# DDC.net
KiCad netlist of a schematic drawn in Altium Designer
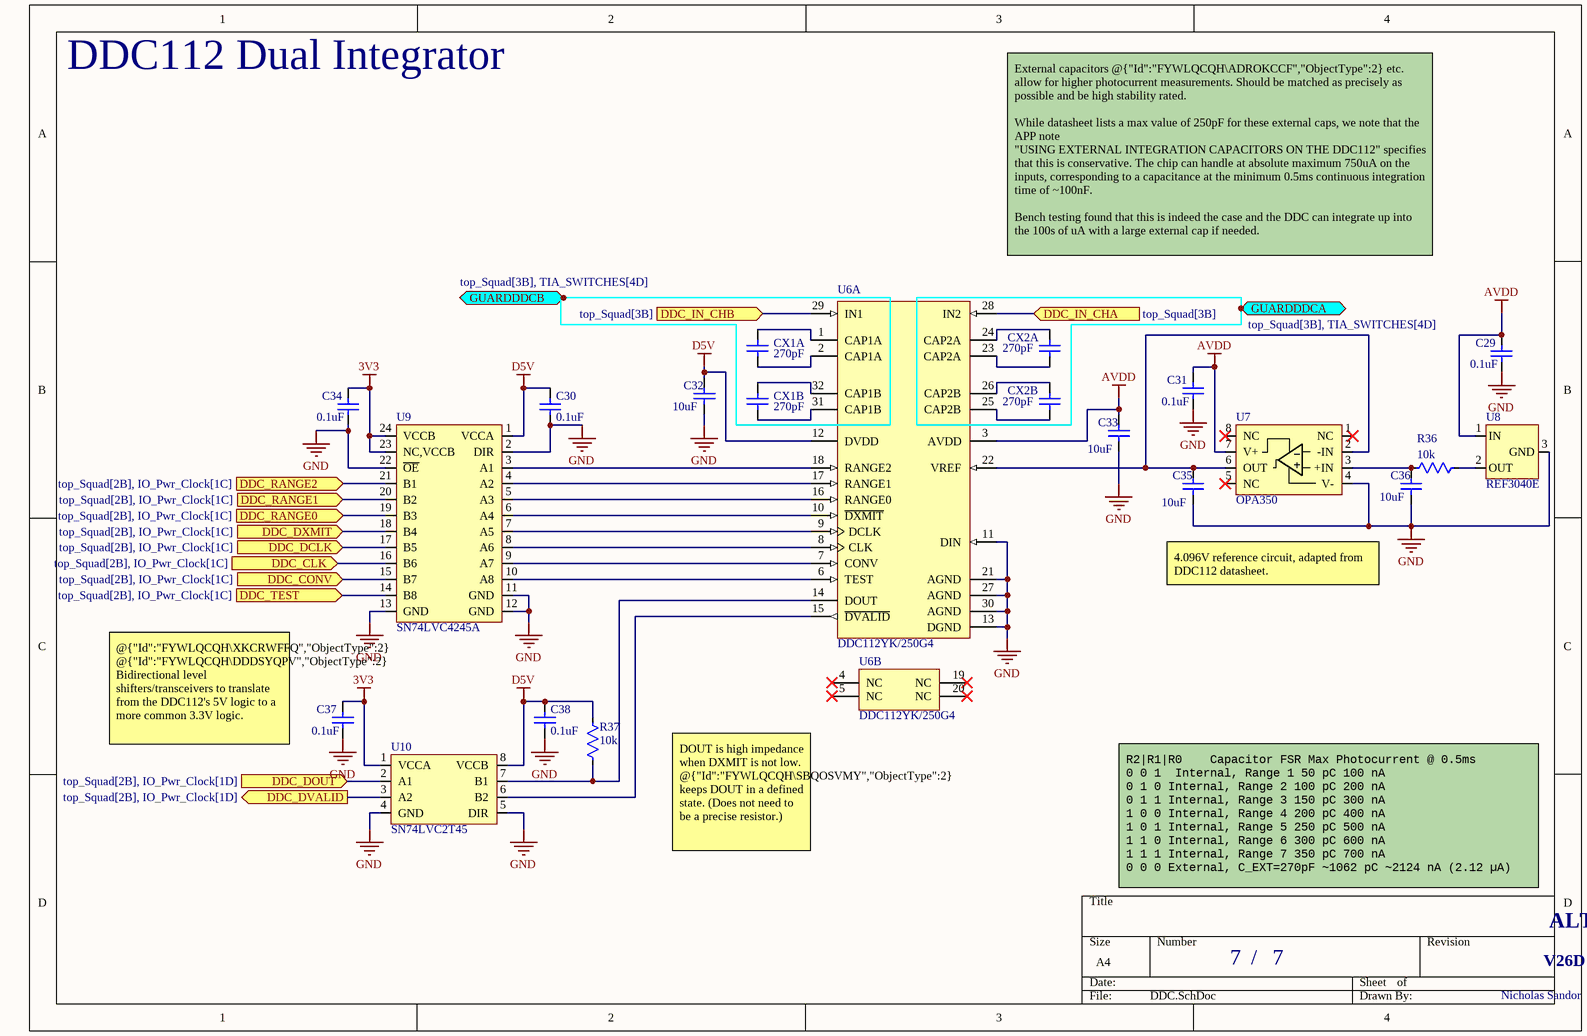
[diagram p0: DDC.SchDoc]

(export (version "E")
  (design (tool "Eeschema 10.0.6"))
  (components
    (comp (ref "C29")
      (value "0.1uF")
      (footprint "CAP 0603 IPC MID DENSITY")
      (description "Kemet C0603C104K5RACAUTO - Cap Ceramic 0.1uF 50V X7R 10% 0603 125C Paper T/R")
      (fields (field (name "MF") "KEMET") (field (name "MP") "C0603C104K5RACAUTO"))
      (libsource (lib "DDC112_Components") (part "CAP"))
    )
    (comp (ref "C30")
      (value "0.1uF")
      (footprint "CAP 0603 IPC MID DENSITY")
      (description "Kemet C0603C104K5RACAUTO - Cap Ceramic 0.1uF 50V X7R 10% 0603 125C Paper T/R")
      (fields (field (name "MF") "KEMET") (field (name "MP") "C0603C104K5RACAUTO"))
      (libsource (lib "DDC112_Components") (part "CAP"))
    )
    (comp (ref "C31")
      (value "0.1uF")
      (footprint "CAP 0603 IPC MID DENSITY")
      (description "Kemet C0603C104K5RACAUTO - Cap Ceramic 0.1uF 50V X7R 10% 0603 125C Paper T/R")
      (fields (field (name "MF") "KEMET") (field (name "MP") "C0603C104K5RACAUTO"))
      (libsource (lib "DDC112_Components") (part "CAP"))
    )
    (comp (ref "C32")
      (value "10uF")
      (footprint "CAP 0805 IPC MID DENSITY")
      (description "Murata GRM21BR61E106KA73L - Cap Ceramic 10uF 10% 25V X5R 0805")
      (fields (field (name "MF") "Murata") (field (name "MP") "GRM21BR61E106KA73L"))
      (libsource (lib "DDC112_Components") (part "CAP"))
    )
    (comp (ref "C33")
      (value "10uF")
      (footprint "CAP 0805 IPC MID DENSITY")
      (description "Murata GRM21BR61E106KA73L - Cap Ceramic 10uF 10% 25V X5R 0805")
      (fields (field (name "MF") "Murata") (field (name "MP") "GRM21BR61E106KA73L"))
      (libsource (lib "DDC112_Components") (part "CAP"))
    )
    (comp (ref "C34")
      (value "0.1uF")
      (footprint "CAP 0603 IPC MID DENSITY")
      (description "Kemet C0603C104K5RACAUTO - Cap Ceramic 0.1uF 50V X7R 10% 0603 125C Paper T/R")
      (fields (field (name "MF") "KEMET") (field (name "MP") "C0603C104K5RACAUTO"))
      (libsource (lib "DDC112_Components") (part "CAP"))
    )
    (comp (ref "C35")
      (value "10uF")
      (footprint "CAP 0805 IPC MID DENSITY")
      (description "Murata GRM21BR61E106KA73L - Cap Ceramic 10uF 10% 25V X5R 0805")
      (fields (field (name "MF") "Murata") (field (name "MP") "GRM21BR61E106KA73L"))
      (libsource (lib "DDC112_Components") (part "CAP"))
    )
    (comp (ref "C36")
      (value "10uF")
      (footprint "CAP 0805 IPC MID DENSITY")
      (description "Murata GRM21BR61E106KA73L - Cap Ceramic 10uF 10% 25V X5R 0805")
      (fields (field (name "MF") "Murata") (field (name "MP") "GRM21BR61E106KA73L"))
      (libsource (lib "DDC112_Components") (part "CAP"))
    )
    (comp (ref "C37")
      (value "0.1uF")
      (footprint "CAP 0603 IPC MID DENSITY")
      (description "Kemet C0603C104K5RACAUTO - Cap Ceramic 0.1uF 50V X7R 10% 0603 125C Paper T/R")
      (fields (field (name "MF") "KEMET") (field (name "MP") "C0603C104K5RACAUTO"))
      (libsource (lib "DDC112_Components") (part "CAP"))
    )
    (comp (ref "C38")
      (value "0.1uF")
      (footprint "CAP 0603 IPC MID DENSITY")
      (description "Kemet C0603C104K5RACAUTO - Cap Ceramic 0.1uF 50V X7R 10% 0603 125C Paper T/R")
      (fields (field (name "MF") "KEMET") (field (name "MP") "C0603C104K5RACAUTO"))
      (libsource (lib "DDC112_Components") (part "CAP"))
    )
    (comp (ref "CX1A")
      (value "270pF")
      (footprint "CAP 1206 NON-IPC KEMET NP0")
      (description "Yageo CC1206FRNPO9BN271 - Cap Ceramic 270pF 1% C0G/NP0 50V SMD 1206")
      (fields (field (name "MF") "YAGEO") (field (name "MP") "CC1206FRNPO9BN271"))
      (libsource (lib "DDC112_Components") (part "CAP"))
    )
    (comp (ref "CX1B")
      (value "270pF")
      (footprint "CAP 1206 NON-IPC KEMET NP0")
      (description "Yageo CC1206FRNPO9BN271 - Cap Ceramic 270pF 1% C0G/NP0 50V SMD 1206")
      (fields (field (name "MF") "YAGEO") (field (name "MP") "CC1206FRNPO9BN271"))
      (libsource (lib "DDC112_Components") (part "CAP"))
    )
    (comp (ref "CX2A")
      (value "270pF")
      (footprint "CAP 1206 NON-IPC KEMET NP0")
      (description "Yageo CC1206FRNPO9BN271 - Cap Ceramic 270pF 1% C0G/NP0 50V SMD 1206")
      (fields (field (name "MF") "YAGEO") (field (name "MP") "CC1206FRNPO9BN271"))
      (libsource (lib "DDC112_Components") (part "CAP"))
    )
    (comp (ref "CX2B")
      (value "270pF")
      (footprint "CAP 1206 NON-IPC KEMET NP0")
      (description "Yageo CC1206FRNPO9BN271 - Cap Ceramic 270pF 1% C0G/NP0 50V SMD 1206")
      (fields (field (name "MF") "YAGEO") (field (name "MP") "CC1206FRNPO9BN271"))
      (libsource (lib "DDC112_Components") (part "CAP"))
    )
    (comp (ref "R36")
      (value "10k")
      (footprint "RES 0603 IPC MID DENSITY")
      (description "Res, Any, Manually select footprint")
      (fields (field (name "MF") "Panasonic Industry") (field (name "MP") "ERJ-3AEB103V"))
      (libsource (lib "DDC112_Components") (part "RES"))
    )
    (comp (ref "R37")
      (value "10k")
      (footprint "RES 0603 IPC MID DENSITY")
      (description "Res, Any, Manually select footprint")
      (fields (field (name "MF") "Panasonic Industry") (field (name "MP") "ERJ-3AEB103V"))
      (libsource (lib "DDC112_Components") (part "RES"))
    )
    (comp (ref "U6")
      (value "DDC112YK/250G4")
      (footprint "TI-PJT32_N")
      (description "Dual Current Input 20-Bit ADC, 0 to 70 degC, 32-pin QFP (PJT32), Green (RoHS & no Sb/Br)")
      (fields (field (name "MANUFACTURER") "Texas Instruments"))
      (libsource (lib "ALTAIR_PD_Amplifiers") (part "CMP-0003-01894-1"))
    )
    (comp (ref "U7")
      (value "OPA350")
      (footprint "8VSSOP LOW DENSITY TI")
      (description "High-Speed Single-Supply Rail-to-Rail Op Amp, MicroAmplifier Series, 8VSSOP")
      (fields (field (name "MF") "Texas Instruments") (field (name "MP") "OPA350EA/2K5"))
      (libsource (lib "ALTAIR_PD_Amplifiers") (part "OPA350EA"))
    )
    (comp (ref "U8")
      (value "REF3040E")
      (footprint "SOT23-3 MID DENSITY TI")
      (description "Low-Drift Low-Power Series Voltage Reference 4.096V SOT23-3")
      (fields (field (name "MF") "Texas Instruments") (field (name "MP") "REF3040EAIDBZR"))
      (libsource (lib "ALTAIR_PD_MiscPower") (part "REF3040EAIDBZR"))
    )
    (comp (ref "U9")
      (value "SN74LVC4245A")
      (footprint "24TSSOP LOW DENSITY TI")
      (description "Octal Bus Transceiver and 3.3V to 5V Shifter with Tri-State Outputs 24TSSOP")
      (fields (field (name "MF") "Texas Instruments") (field (name "MP") "SN74LVC4245APWR"))
      (libsource (lib "DDC112_Components") (part "SN74LVC4245A"))
    )
    (comp (ref "U10")
      (value "SN74LVC2T45")
      (footprint "DCU8-L")
      (description "Dual-Bit Dual-Supply Bus Transceiver With Configurable Voltage Translation 8VSSOP")
      (fields (field (name "MF") "Texas Instruments") (field (name "MP") "SN74LVC2T45DCUR"))
      (libsource (lib "DDC112_Components") (part "SN74LVC2T45"))
    )
  )
  (nets
    (net (code "1") (name "/DDC_CLK") (class "Default")
      (node (ref "U9") (pin "16") (pinfunction "B6_16") (pintype "passive"))
    )
    (net (code "2") (name "/DDC_CONV") (class "Default")
      (node (ref "U9") (pin "15") (pinfunction "B7_15") (pintype "passive"))
    )
    (net (code "3") (name "/DDC_DCLK") (class "Default")
      (node (ref "U9") (pin "17") (pinfunction "B5_17") (pintype "passive"))
    )
    (net (code "4") (name "/DDC_DOUT") (class "Default")
      (node (ref "U10") (pin "2") (pinfunction "A1_2") (pintype "passive"))
    )
    (net (code "5") (name "/DDC_DVALID") (class "Default")
      (node (ref "U10") (pin "3") (pinfunction "A2_3") (pintype "passive"))
    )
    (net (code "6") (name "/DDC_DXMIT") (class "Default")
      (node (ref "U9") (pin "18") (pinfunction "B4_18") (pintype "passive"))
    )
    (net (code "7") (name "/DDC_IN_CHA") (class "Default")
      (node (ref "U6") (pin "28") (pinfunction "IN2_28") (pintype "input"))
    )
    (net (code "8") (name "/DDC_IN_CHB") (class "Default")
      (node (ref "U6") (pin "29") (pinfunction "IN1_29") (pintype "input"))
    )
    (net (code "9") (name "/DDC_RANGE0") (class "Default")
      (node (ref "U9") (pin "19") (pinfunction "B3_19") (pintype "passive"))
    )
    (net (code "10") (name "/DDC_RANGE1") (class "Default")
      (node (ref "U9") (pin "20") (pinfunction "B2_20") (pintype "passive"))
    )
    (net (code "11") (name "/DDC_RANGE2") (class "Default")
      (node (ref "U9") (pin "21") (pinfunction "B1_21") (pintype "passive"))
    )
    (net (code "12") (name "/DDC_TEST") (class "Default")
      (node (ref "U9") (pin "14") (pinfunction "B8_14") (pintype "passive"))
    )
    (net (code "15") (name "3V3") (class "Default")
      (node (ref "C34") (pin "1") (pinfunction "1_1") (pintype "passive"))
      (node (ref "C37") (pin "1") (pinfunction "1_1") (pintype "passive"))
      (node (ref "U10") (pin "1") (pinfunction "VCCA_1") (pintype "passive"))
      (node (ref "U9") (pin "23") (pinfunction "NC,VCCB_23") (pintype "passive"))
      (node (ref "U9") (pin "24") (pinfunction "VCCB_24") (pintype "passive"))
    )
    (net (code "16") (name "AVDD") (class "Default")
      (node (ref "C29") (pin "2") (pinfunction "2_2") (pintype "passive"))
      (node (ref "C31") (pin "2") (pinfunction "2_2") (pintype "passive"))
      (node (ref "C33") (pin "1") (pinfunction "1_1") (pintype "passive"))
      (node (ref "U6") (pin "3") (pinfunction "AVDD_3") (pintype "power_in"))
      (node (ref "U7") (pin "7") (pinfunction "V+_7") (pintype "passive"))
      (node (ref "U8") (pin "1") (pinfunction "IN_1") (pintype "passive"))
    )
    (net (code "17") (name "D5V") (class "Default")
      (node (ref "C30") (pin "1") (pinfunction "1_1") (pintype "passive"))
      (node (ref "C32") (pin "1") (pinfunction "1_1") (pintype "passive"))
      (node (ref "C38") (pin "1") (pinfunction "1_1") (pintype "passive"))
      (node (ref "R37") (pin "2") (pinfunction "2_2") (pintype "passive"))
      (node (ref "U10") (pin "8") (pinfunction "VCCB_8") (pintype "passive"))
      (node (ref "U6") (pin "12") (pinfunction "DVDD_12") (pintype "power_in"))
      (node (ref "U9") (pin "1") (pinfunction "VCCA_1") (pintype "passive"))
    )
    (net (code "18") (name "GND") (class "Default")
      (node (ref "C29") (pin "1") (pinfunction "1_1") (pintype "passive"))
      (node (ref "C30") (pin "2") (pinfunction "2_2") (pintype "passive"))
      (node (ref "C31") (pin "1") (pinfunction "1_1") (pintype "passive"))
      (node (ref "C32") (pin "2") (pinfunction "2_2") (pintype "passive"))
      (node (ref "C33") (pin "2") (pinfunction "2_2") (pintype "passive"))
      (node (ref "C34") (pin "2") (pinfunction "2_2") (pintype "passive"))
      (node (ref "C35") (pin "2") (pinfunction "2_2") (pintype "passive"))
      (node (ref "C36") (pin "2") (pinfunction "2_2") (pintype "passive"))
      (node (ref "C37") (pin "2") (pinfunction "2_2") (pintype "passive"))
      (node (ref "C38") (pin "2") (pinfunction "2_2") (pintype "passive"))
      (node (ref "U10") (pin "4") (pinfunction "GND_4") (pintype "passive"))
      (node (ref "U10") (pin "5") (pinfunction "DIR_5") (pintype "passive"))
      (node (ref "U6") (pin "11") (pinfunction "DIN_11") (pintype "input"))
      (node (ref "U6") (pin "13") (pinfunction "DGND_13") (pintype "power_in"))
      (node (ref "U6") (pin "21") (pinfunction "AGND_21") (pintype "power_in"))
      (node (ref "U6") (pin "27") (pinfunction "AGND_27") (pintype "power_in"))
      (node (ref "U6") (pin "30") (pinfunction "AGND_30") (pintype "power_in"))
      (node (ref "U7") (pin "4") (pinfunction "V-_4") (pintype "passive"))
      (node (ref "U8") (pin "3") (pinfunction "GND_3") (pintype "passive"))
      (node (ref "U9") (pin "11") (pinfunction "GND_11") (pintype "passive"))
      (node (ref "U9") (pin "12") (pinfunction "GND_12") (pintype "passive"))
      (node (ref "U9") (pin "13") (pinfunction "GND_13") (pintype "passive"))
      (node (ref "U9") (pin "2") (pinfunction "DIR_2") (pintype "passive"))
      (node (ref "U9") (pin "22") (pinfunction "~{OE}_22") (pintype "passive"))
    )
    (net (code "19") (name "Net-(CX1A-Pad1)") (class "Default")
      (node (ref "CX1A") (pin "1") (pinfunction "1_1") (pintype "passive"))
      (node (ref "U6") (pin "2") (pinfunction "CAP1A_2") (pintype "passive"))
    )
    (net (code "20") (name "Net-(CX1A-Pad2)") (class "Default")
      (node (ref "CX1A") (pin "2") (pinfunction "2_2") (pintype "passive"))
      (node (ref "U6") (pin "1") (pinfunction "CAP1A_1") (pintype "passive"))
    )
    (net (code "21") (name "Net-(CX1B-Pad1)") (class "Default")
      (node (ref "CX1B") (pin "1") (pinfunction "1_1") (pintype "passive"))
      (node (ref "U6") (pin "31") (pinfunction "CAP1B_31") (pintype "passive"))
    )
    (net (code "22") (name "Net-(CX1B-Pad2)") (class "Default")
      (node (ref "CX1B") (pin "2") (pinfunction "2_2") (pintype "passive"))
      (node (ref "U6") (pin "32") (pinfunction "CAP1B_32") (pintype "passive"))
    )
    (net (code "23") (name "Net-(CX2A-Pad1)") (class "Default")
      (node (ref "CX2A") (pin "1") (pinfunction "1_1") (pintype "passive"))
      (node (ref "U6") (pin "23") (pinfunction "CAP2A_23") (pintype "passive"))
    )
    (net (code "24") (name "Net-(CX2A-Pad2)") (class "Default")
      (node (ref "CX2A") (pin "2") (pinfunction "2_2") (pintype "passive"))
      (node (ref "U6") (pin "24") (pinfunction "CAP2A_24") (pintype "passive"))
    )
    (net (code "25") (name "Net-(CX2B-Pad1)") (class "Default")
      (node (ref "CX2B") (pin "1") (pinfunction "1_1") (pintype "passive"))
      (node (ref "U6") (pin "25") (pinfunction "CAP2B_25") (pintype "passive"))
    )
    (net (code "26") (name "Net-(CX2B-Pad2)") (class "Default")
      (node (ref "CX2B") (pin "2") (pinfunction "2_2") (pintype "passive"))
      (node (ref "U6") (pin "26") (pinfunction "CAP2B_26") (pintype "passive"))
    )
    (net (code "27") (name "Net-(U6A-CLK)") (class "Default")
      (node (ref "U6") (pin "8") (pinfunction "CLK_8") (pintype "input"))
      (node (ref "U9") (pin "8") (pinfunction "A6_8") (pintype "passive"))
    )
    (net (code "28") (name "Net-(U6A-CONV)") (class "Default")
      (node (ref "U6") (pin "7") (pinfunction "CONV_7") (pintype "input"))
      (node (ref "U9") (pin "9") (pinfunction "A7_9") (pintype "passive"))
    )
    (net (code "29") (name "Net-(U6A-DCLK)") (class "Default")
      (node (ref "U6") (pin "9") (pinfunction "DCLK_9") (pintype "input"))
      (node (ref "U9") (pin "7") (pinfunction "A5_7") (pintype "passive"))
    )
    (net (code "30") (name "Net-(U6A-RANGE0)") (class "Default")
      (node (ref "U6") (pin "16") (pinfunction "RANGE0_16") (pintype "input"))
      (node (ref "U9") (pin "5") (pinfunction "A3_5") (pintype "passive"))
    )
    (net (code "31") (name "Net-(U6A-RANGE1)") (class "Default")
      (node (ref "U6") (pin "17") (pinfunction "RANGE1_17") (pintype "input"))
      (node (ref "U9") (pin "4") (pinfunction "A2_4") (pintype "passive"))
    )
    (net (code "32") (name "Net-(U6A-RANGE2)") (class "Default")
      (node (ref "U6") (pin "18") (pinfunction "RANGE2_18") (pintype "input"))
      (node (ref "U9") (pin "3") (pinfunction "A1_3") (pintype "passive"))
    )
    (net (code "33") (name "Net-(U6A-TEST)") (class "Default")
      (node (ref "U6") (pin "6") (pinfunction "TEST_6") (pintype "input"))
      (node (ref "U9") (pin "10") (pinfunction "A8_10") (pintype "passive"))
    )
    (net (code "34") (name "Net-(U6A-VREF)") (class "Default")
      (node (ref "C35") (pin "1") (pinfunction "1_1") (pintype "passive"))
      (node (ref "U6") (pin "22") (pinfunction "VREF_22") (pintype "input"))
      (node (ref "U7") (pin "2") (pinfunction "-IN_2") (pintype "passive"))
      (node (ref "U7") (pin "6") (pinfunction "OUT_6") (pintype "passive"))
    )
    (net (code "35") (name "Net-(U6A-~{DXMIT})") (class "Default")
      (node (ref "U6") (pin "10") (pinfunction "~{DXMIT}_10") (pintype "input"))
      (node (ref "U9") (pin "6") (pinfunction "A4_6") (pintype "passive"))
    )
    (net (code "36") (name "Net-(U7-+IN)") (class "Default")
      (node (ref "C36") (pin "1") (pinfunction "1_1") (pintype "passive"))
      (node (ref "R36") (pin "1") (pinfunction "1_1") (pintype "passive"))
      (node (ref "U7") (pin "3") (pinfunction "+IN_3") (pintype "passive"))
    )
    (net (code "37") (name "Net-(U8-OUT)") (class "Default")
      (node (ref "R36") (pin "2") (pinfunction "2_2") (pintype "passive"))
      (node (ref "U8") (pin "2") (pinfunction "OUT_2") (pintype "passive"))
    )
    (net (code "38") (name "Net-(U10-B1)") (class "Default")
      (node (ref "R37") (pin "1") (pinfunction "1_1") (pintype "passive"))
      (node (ref "U10") (pin "7") (pinfunction "B1_7") (pintype "passive"))
      (node (ref "U6") (pin "14") (pinfunction "DOUT_14") (pintype "tri_state"))
    )
    (net (code "39") (name "Net-(U10-B2)") (class "Default")
      (node (ref "U10") (pin "6") (pinfunction "B2_6") (pintype "passive"))
      (node (ref "U6") (pin "15") (pinfunction "~{DVALID}_15") (pintype "output"))
    )
    (net (code "40") (name "unconnected-(U6B-NC-Pad4)") (class "Default")
      (node (ref "U6") (pin "4") (pinfunction "NC_4") (pintype "passive+no_connect"))
    )
    (net (code "41") (name "unconnected-(U6B-NC-Pad5)") (class "Default")
      (node (ref "U6") (pin "5") (pinfunction "NC_5") (pintype "passive+no_connect"))
    )
    (net (code "42") (name "unconnected-(U6B-NC-Pad19)") (class "Default")
      (node (ref "U6") (pin "19") (pinfunction "NC_19") (pintype "passive+no_connect"))
    )
    (net (code "43") (name "unconnected-(U6B-NC-Pad20)") (class "Default")
      (node (ref "U6") (pin "20") (pinfunction "NC_20") (pintype "passive+no_connect"))
    )
    (net (code "44") (name "unconnected-(U7-NC-Pad1)") (class "Default")
      (node (ref "U7") (pin "1") (pinfunction "NC_1") (pintype "passive+no_connect"))
    )
    (net (code "45") (name "unconnected-(U7-NC-Pad5)") (class "Default")
      (node (ref "U7") (pin "5") (pinfunction "NC_5") (pintype "passive+no_connect"))
    )
    (net (code "46") (name "unconnected-(U7-NC-Pad8)") (class "Default")
      (node (ref "U7") (pin "8") (pinfunction "NC_8") (pintype "passive+no_connect"))
    )
  )
)
